# tugas0_Aziz_Mustofa_13214027.net
KiCad netlist of a schematic drawn in EAGLE
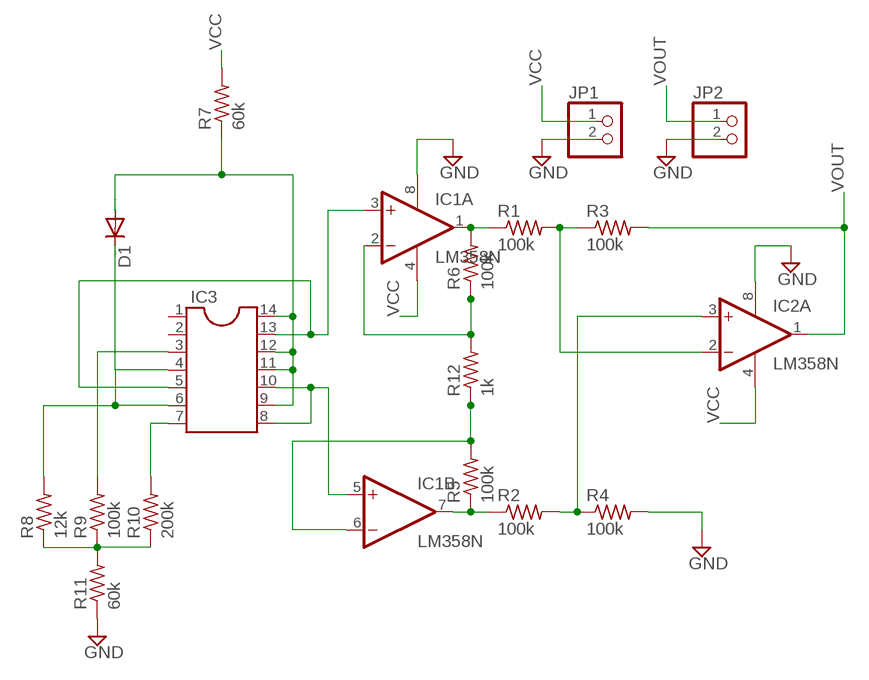
[diagram p0: schematic, sheet 1]

(export (version "E")
  (design (tool "Eeschema 10.0.6"))
  (components
    (comp (ref "D1")
      (value "DIODE-D-7.5")
      (footprint "eagle-import:D-7.5")
      (libsource (lib "eagle-import") (part "DIODE-D-7.5"))
    )
    (comp (ref "IC1")
      (value "LM358N")
      (footprint "eagle-import:DIL08")
      (libsource (lib "eagle-import") (part "LM358N"))
    )
    (comp (ref "IC2")
      (value "LM358N")
      (footprint "eagle-import:DIL08")
      (libsource (lib "eagle-import") (part "LM358N"))
    )
    (comp (ref "IC3")
      (value "DIL14")
      (footprint "eagle-import:DIL14")
      (libsource (lib "eagle-import") (part "DIL14"))
    )
    (comp (ref "JP1")
      (value "PINHD-1X2")
      (footprint "eagle-import:1X02")
      (libsource (lib "eagle-import") (part "PINHD-1X2"))
    )
    (comp (ref "JP2")
      (value "PINHD-1X2")
      (footprint "eagle-import:1X02")
      (libsource (lib "eagle-import") (part "PINHD-1X2"))
    )
    (comp (ref "R1")
      (value "100k")
      (footprint "eagle-import:0204_7")
      (libsource (lib "eagle-import") (part "R-US_0204/7"))
    )
    (comp (ref "R2")
      (value "100k")
      (footprint "eagle-import:0204_7")
      (libsource (lib "eagle-import") (part "R-US_0204/7"))
    )
    (comp (ref "R3")
      (value "100k")
      (footprint "eagle-import:0204_7")
      (libsource (lib "eagle-import") (part "R-US_0204/7"))
    )
    (comp (ref "R4")
      (value "100k")
      (footprint "eagle-import:0204_7")
      (libsource (lib "eagle-import") (part "R-US_0204/7"))
    )
    (comp (ref "R5")
      (value "100k")
      (footprint "eagle-import:0204_7")
      (libsource (lib "eagle-import") (part "R-US_0204/7"))
    )
    (comp (ref "R6")
      (value "100k")
      (footprint "eagle-import:0204_7")
      (libsource (lib "eagle-import") (part "R-US_0204/7"))
    )
    (comp (ref "R7")
      (value "60k")
      (footprint "eagle-import:0204_7")
      (libsource (lib "eagle-import") (part "R-US_0204/7"))
    )
    (comp (ref "R8")
      (value "12k")
      (footprint "eagle-import:0204_7")
      (libsource (lib "eagle-import") (part "R-US_0204/7"))
    )
    (comp (ref "R9")
      (value "100k")
      (footprint "eagle-import:0204_7")
      (libsource (lib "eagle-import") (part "R-US_0204/7"))
    )
    (comp (ref "R10")
      (value "200k")
      (footprint "eagle-import:0204_7")
      (libsource (lib "eagle-import") (part "R-US_0204/7"))
    )
    (comp (ref "R11")
      (value "60k")
      (footprint "eagle-import:0204_7")
      (libsource (lib "eagle-import") (part "R-US_0204/7"))
    )
    (comp (ref "R12")
      (value "1k")
      (footprint "eagle-import:0204_7")
      (libsource (lib "eagle-import") (part "R-US_0204/7"))
    )
  )
  (nets
    (net (code "1") (name "/VCC") (class "Default")
      (node (ref "JP1") (pin "1") (pinfunction "1_1") (pintype "passive"))
      (node (ref "R7") (pin "2") (pinfunction "2_2") (pintype "passive"))
    )
    (net (code "2") (name "/VOUT") (class "Default")
      (node (ref "IC2") (pin "1") (pinfunction "OUT_1") (pintype "output"))
      (node (ref "JP2") (pin "1") (pinfunction "1_1") (pintype "passive"))
      (node (ref "R3") (pin "2") (pinfunction "2_2") (pintype "passive"))
    )
    (net (code "3") (name "GND") (class "Default")
      (node (ref "IC1") (pin "8") (pinfunction "V+_8") (pintype "power_in"))
      (node (ref "IC2") (pin "8") (pinfunction "V+_8") (pintype "power_in"))
      (node (ref "JP1") (pin "2") (pinfunction "2_2") (pintype "passive"))
      (node (ref "JP2") (pin "2") (pinfunction "2_2") (pintype "passive"))
      (node (ref "R11") (pin "1") (pinfunction "1_1") (pintype "passive"))
      (node (ref "R4") (pin "2") (pinfunction "2_2") (pintype "passive"))
    )
    (net (code "4") (name "Net-(D1-PadA)") (class "Default")
      (node (ref "D1") (pin "A") (pinfunction "A_A") (pintype "passive"))
      (node (ref "IC3") (pin "11") (pinfunction "11_11") (pintype "passive"))
      (node (ref "IC3") (pin "12") (pinfunction "12_12") (pintype "passive"))
      (node (ref "IC3") (pin "14") (pinfunction "14_14") (pintype "passive"))
      (node (ref "IC3") (pin "9") (pinfunction "9_9") (pintype "passive"))
      (node (ref "R7") (pin "1") (pinfunction "1_1") (pintype "passive"))
    )
    (net (code "5") (name "Net-(D1-PadC)") (class "Default")
      (node (ref "D1") (pin "C") (pinfunction "C_C") (pintype "passive"))
      (node (ref "IC3") (pin "4") (pinfunction "4_4") (pintype "passive"))
      (node (ref "IC3") (pin "6") (pinfunction "6_6") (pintype "passive"))
      (node (ref "R8") (pin "2") (pinfunction "2_2") (pintype "passive"))
    )
    (net (code "6") (name "Net-(IC1A-+IN)") (class "Default")
      (node (ref "IC1") (pin "3") (pinfunction "+IN_3") (pintype "input"))
      (node (ref "IC3") (pin "13") (pinfunction "13_13") (pintype "passive"))
      (node (ref "IC3") (pin "5") (pinfunction "5_5") (pintype "passive"))
    )
    (net (code "7") (name "Net-(IC1A--IN)") (class "Default")
      (node (ref "IC1") (pin "2") (pinfunction "-IN_2") (pintype "input"))
      (node (ref "R12") (pin "2") (pinfunction "2_2") (pintype "passive"))
      (node (ref "R6") (pin "1") (pinfunction "1_1") (pintype "passive"))
    )
    (net (code "8") (name "Net-(IC1A-OUT)") (class "Default")
      (node (ref "IC1") (pin "1") (pinfunction "OUT_1") (pintype "output"))
      (node (ref "R1") (pin "1") (pinfunction "1_1") (pintype "passive"))
      (node (ref "R6") (pin "2") (pinfunction "2_2") (pintype "passive"))
    )
    (net (code "9") (name "Net-(IC1B-+IN)") (class "Default")
      (node (ref "IC1") (pin "5") (pinfunction "+IN_5") (pintype "input"))
      (node (ref "IC3") (pin "10") (pinfunction "10_10") (pintype "passive"))
      (node (ref "IC3") (pin "8") (pinfunction "8_8") (pintype "passive"))
    )
    (net (code "10") (name "Net-(IC1B--IN)") (class "Default")
      (node (ref "IC1") (pin "6") (pinfunction "-IN_6") (pintype "input"))
      (node (ref "R12") (pin "1") (pinfunction "1_1") (pintype "passive"))
      (node (ref "R5") (pin "2") (pinfunction "2_2") (pintype "passive"))
    )
    (net (code "11") (name "Net-(IC1B-OUT)") (class "Default")
      (node (ref "IC1") (pin "7") (pinfunction "OUT_7") (pintype "output"))
      (node (ref "R2") (pin "1") (pinfunction "1_1") (pintype "passive"))
      (node (ref "R5") (pin "1") (pinfunction "1_1") (pintype "passive"))
    )
    (net (code "12") (name "Net-(IC2A-+IN)") (class "Default")
      (node (ref "IC2") (pin "3") (pinfunction "+IN_3") (pintype "input"))
      (node (ref "R2") (pin "2") (pinfunction "2_2") (pintype "passive"))
      (node (ref "R4") (pin "1") (pinfunction "1_1") (pintype "passive"))
    )
    (net (code "13") (name "Net-(IC2A--IN)") (class "Default")
      (node (ref "IC2") (pin "2") (pinfunction "-IN_2") (pintype "input"))
      (node (ref "R1") (pin "2") (pinfunction "2_2") (pintype "passive"))
      (node (ref "R3") (pin "1") (pinfunction "1_1") (pintype "passive"))
    )
    (net (code "14") (name "Net-(IC3-Pad3)") (class "Default")
      (node (ref "IC3") (pin "3") (pinfunction "3_3") (pintype "passive"))
      (node (ref "R9") (pin "2") (pinfunction "2_2") (pintype "passive"))
    )
    (net (code "15") (name "Net-(IC3-Pad7)") (class "Default")
      (node (ref "IC3") (pin "7") (pinfunction "7_7") (pintype "passive"))
      (node (ref "R10") (pin "2") (pinfunction "2_2") (pintype "passive"))
    )
    (net (code "16") (name "Net-(R10-Pad1)") (class "Default")
      (node (ref "R10") (pin "1") (pinfunction "1_1") (pintype "passive"))
      (node (ref "R11") (pin "2") (pinfunction "2_2") (pintype "passive"))
      (node (ref "R8") (pin "1") (pinfunction "1_1") (pintype "passive"))
      (node (ref "R9") (pin "1") (pinfunction "1_1") (pintype "passive"))
    )
    (net (code "17") (name "unconnected-(IC1C-V--Pad4)") (class "Default")
      (node (ref "IC1") (pin "4") (pinfunction "V-_4") (pintype "power_in"))
    )
    (net (code "18") (name "unconnected-(IC2C-V--Pad4)") (class "Default")
      (node (ref "IC2") (pin "4") (pinfunction "V-_4") (pintype "power_in"))
    )
    (net (code "19") (name "unconnected-(IC3-Pad1)") (class "Default")
      (node (ref "IC3") (pin "1") (pinfunction "1_1") (pintype "passive"))
    )
    (net (code "20") (name "unconnected-(IC3-Pad2)") (class "Default")
      (node (ref "IC3") (pin "2") (pinfunction "2_2") (pintype "passive"))
    )
  )
)
